# ESP8266-PIR.net
KiCad netlist of a schematic drawn in EAGLE
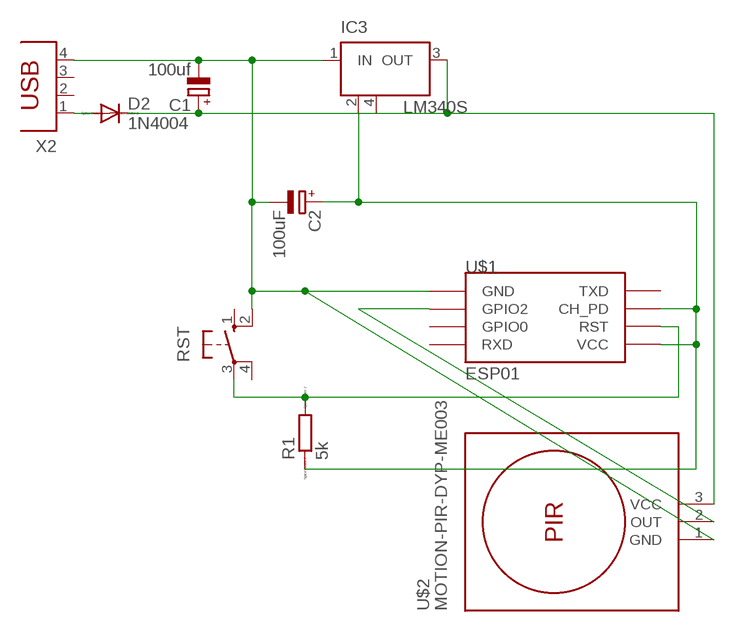
[diagram p0: schematic, sheet 1]

(export (version "E")
  (design (tool "Eeschema 10.0.6"))
  (components
    (comp (ref "C1")
      (value "100uf")
      (footprint "eagle-import:E2,5-5")
      (libsource (lib "eagle-import") (part "CPOL-EUE2.5-5"))
    )
    (comp (ref "C2")
      (value "100uF")
      (footprint "eagle-import:E2,5-5")
      (libsource (lib "eagle-import") (part "CPOL-EUE2.5-5"))
    )
    (comp (ref "D2")
      (value "1N4004")
      (footprint "eagle-import:DO41-10")
      (libsource (lib "eagle-import") (part "1N4004"))
    )
    (comp (ref "IC3")
      (value "LM340S")
      (footprint "eagle-import:SOT223")
      (libsource (lib "eagle-import") (part "LM340S"))
    )
    (comp (ref "R1")
      (value "5k")
      (footprint "eagle-import:0204_7")
      (libsource (lib "eagle-import") (part "R0204/7"))
    )
    (comp (ref "RST")
      (value "10-XX")
      (footprint "eagle-import:B3F-10XX")
      (fields (field (name "MPN") "B3F-1000"))
      (libsource (lib "eagle-import") (part "10-XX"))
    )
    (comp (ref "U$1")
      (value "ESP01")
      (footprint "eagle-import:ESP01")
      (libsource (lib "eagle-import") (part "ESP01"))
    )
    (comp (ref "U$2")
      (value "MOTION-PIR-DYP-ME003")
      (footprint "eagle-import:MOTION-PIR-DYP-ME003")
      (libsource (lib "eagle-import") (part "MOTION-PIR-DYP-ME003"))
    )
    (comp (ref "X2")
      (value "PN61729")
      (footprint "eagle-import:PN61729")
      (libsource (lib "eagle-import") (part "PN61729"))
    )
  )
  (nets
    (net (code "1") (name "/5V") (class "Default")
      (node (ref "C1") (pin "+") (pinfunction "+_+") (pintype "passive"))
      (node (ref "D2") (pin "A") (pinfunction "A_A") (pintype "passive"))
      (node (ref "D2") (pin "C") (pinfunction "C_C") (pintype "passive"))
      (node (ref "IC3") (pin "3") (pinfunction "OUT_3") (pintype "passive"))
      (node (ref "U$2") (pin "3") (pinfunction "VCC_3") (pintype "power_in"))
      (node (ref "X2") (pin "1") (pinfunction "1_1") (pintype "passive"))
    )
    (net (code "2") (name "/GND") (class "Default")
      (node (ref "IC3") (pin "4") (pinfunction "GND_4") (pintype "power_in"))
    )
    (net (code "3") (name "Net-(C2-Pad+)") (class "Default")
      (node (ref "C2") (pin "+") (pinfunction "+_+") (pintype "passive"))
      (node (ref "IC3") (pin "2") (pinfunction "GND_2") (pintype "power_in"))
      (node (ref "R1") (pin "1") (pinfunction "1_1") (pintype "passive"))
      (node (ref "U$1") (pin "CH_PD") (pinfunction "CH_PD_CH_PD") (pintype "bidirectional"))
      (node (ref "U$1") (pin "VCC") (pinfunction "VCC_VCC") (pintype "bidirectional"))
    )
    (net (code "4") (name "Net-(IC3-IN)") (class "Default")
      (node (ref "C1") (pin "-") (pinfunction "-_-") (pintype "passive"))
      (node (ref "C2") (pin "-") (pinfunction "-_-") (pintype "passive"))
      (node (ref "IC3") (pin "1") (pinfunction "IN_1") (pintype "input"))
      (node (ref "RST") (pin "2") (pinfunction "S1_2") (pintype "passive"))
      (node (ref "U$1") (pin "GND") (pinfunction "GND_GND") (pintype "bidirectional"))
      (node (ref "U$2") (pin "1") (pinfunction "GND_1") (pintype "power_in"))
      (node (ref "X2") (pin "4") (pinfunction "4_4") (pintype "passive"))
    )
    (net (code "5") (name "Net-(RST-P)") (class "Default")
      (node (ref "R1") (pin "2") (pinfunction "2_2") (pintype "passive"))
      (node (ref "RST") (pin "3") (pinfunction "P_3") (pintype "passive"))
      (node (ref "U$1") (pin "RST") (pinfunction "RST_RST") (pintype "bidirectional"))
    )
    (net (code "6") (name "Net-(U$2-OUT)") (class "Default")
      (node (ref "U$1") (pin "GPIO2") (pinfunction "GPIO2_GPIO2") (pintype "bidirectional"))
      (node (ref "U$2") (pin "2") (pinfunction "OUT_2") (pintype "output"))
    )
    (net (code "7") (name "unconnected-(RST-P1-Pad4)") (class "Default")
      (node (ref "RST") (pin "4") (pinfunction "P1_4") (pintype "passive"))
    )
    (net (code "8") (name "unconnected-(RST-S-Pad1)") (class "Default")
      (node (ref "RST") (pin "1") (pinfunction "S_1") (pintype "passive"))
    )
    (net (code "9") (name "unconnected-(U$1-PadGPIO0)") (class "Default")
      (node (ref "U$1") (pin "GPIO0") (pinfunction "GPIO0_GPIO0") (pintype "bidirectional"))
    )
    (net (code "10") (name "unconnected-(U$1-RXD-PadRX)") (class "Default")
      (node (ref "U$1") (pin "RX") (pinfunction "RXD_RX") (pintype "bidirectional"))
    )
    (net (code "11") (name "unconnected-(U$1-TXD-PadTX)") (class "Default")
      (node (ref "U$1") (pin "TX") (pinfunction "TXD_TX") (pintype "bidirectional"))
    )
    (net (code "12") (name "unconnected-(X2-Pad2)") (class "Default")
      (node (ref "X2") (pin "2") (pinfunction "2_2") (pintype "passive"))
    )
    (net (code "13") (name "unconnected-(X2-Pad3)") (class "Default")
      (node (ref "X2") (pin "3") (pinfunction "3_3") (pintype "passive"))
    )
  )
)
